# PD_MK2_Signals.net
KiCad netlist of a schematic drawn in Altium Designer
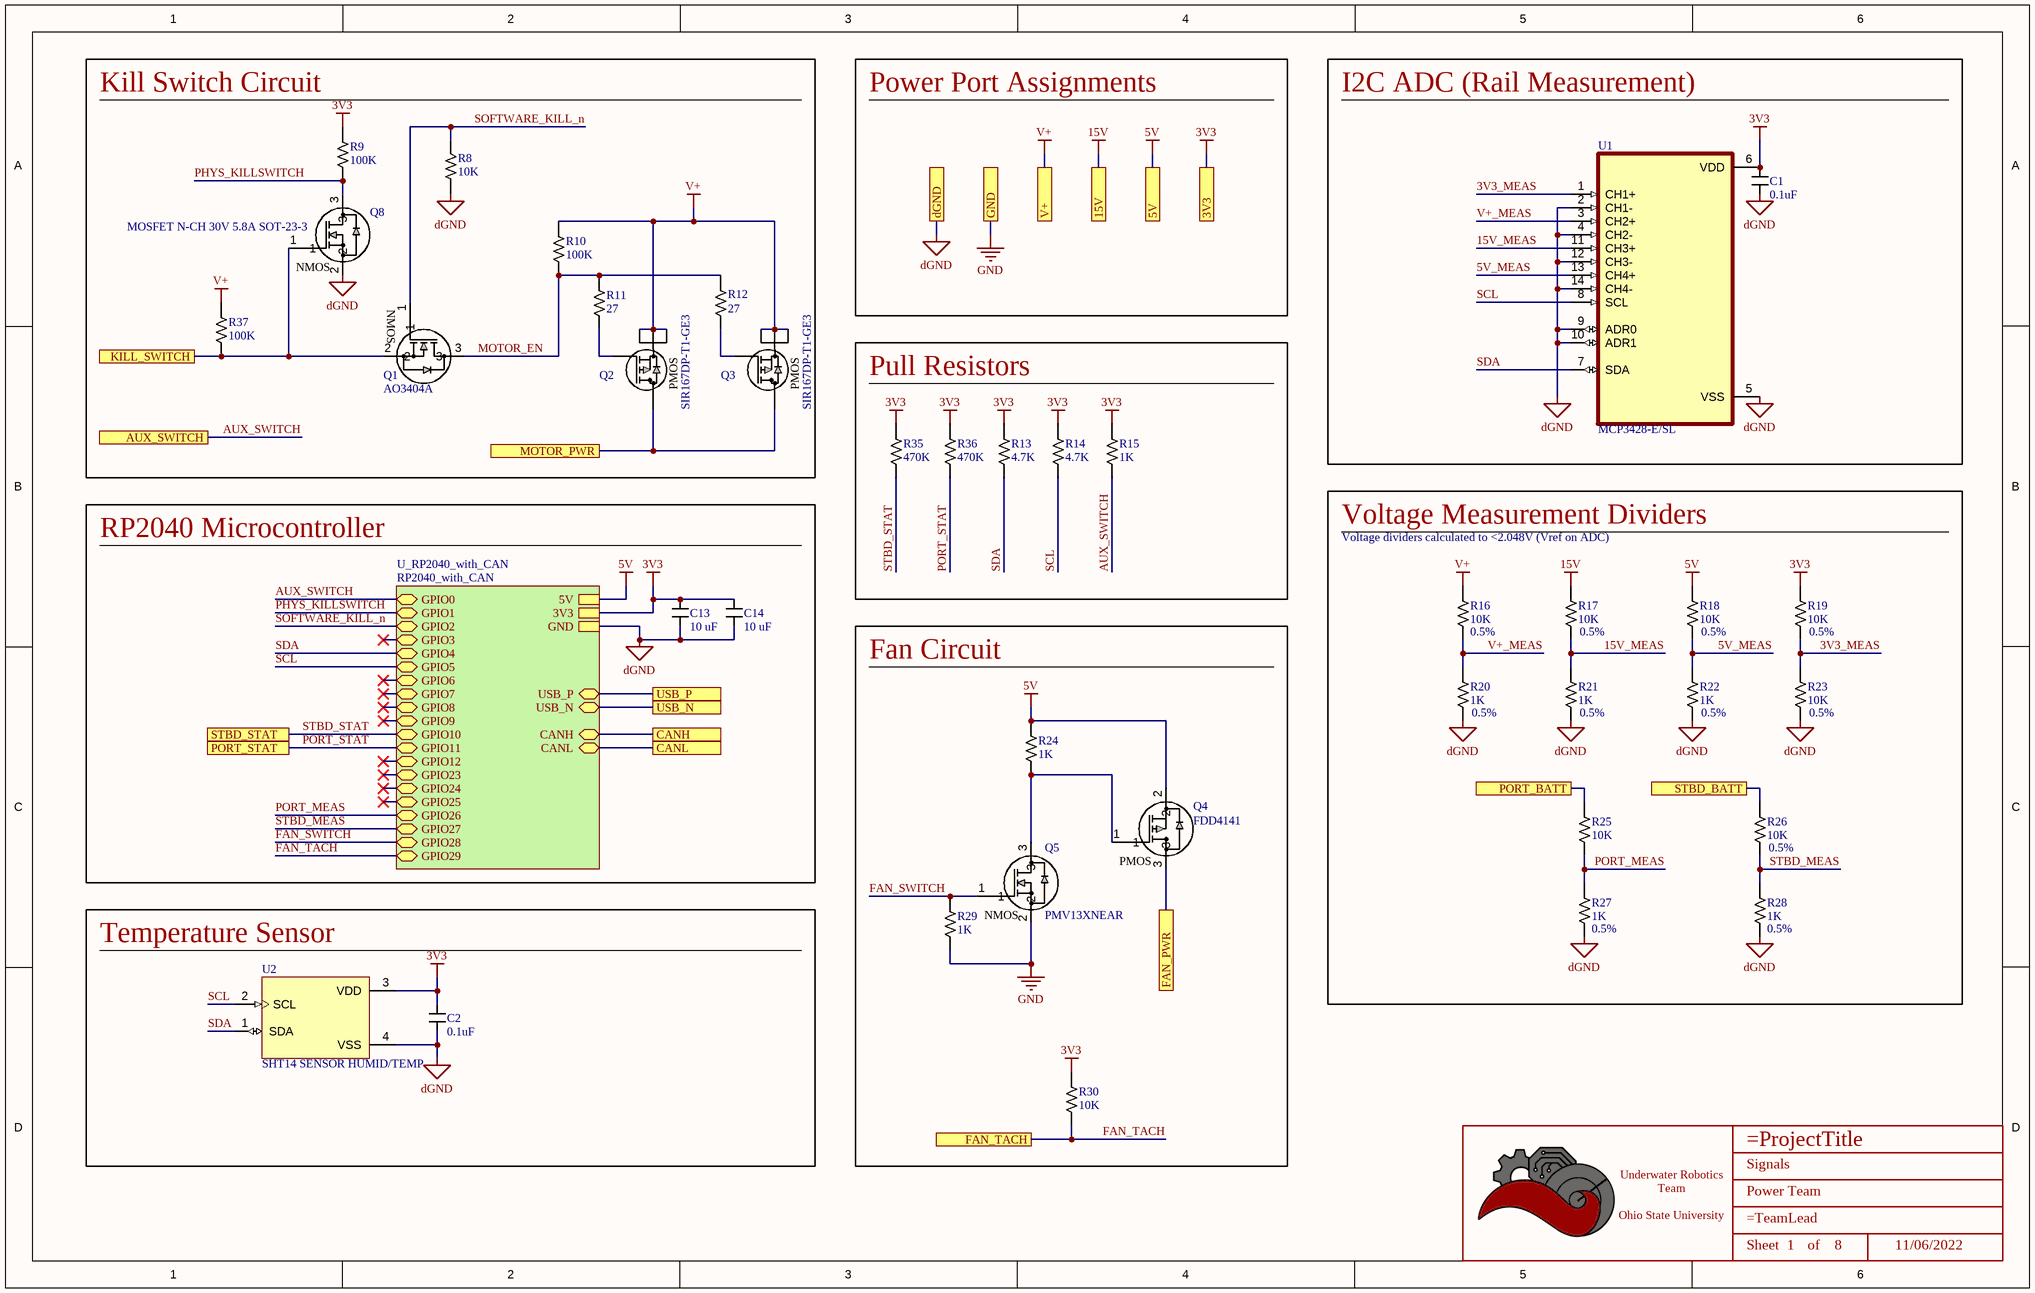
[diagram p0: PD_MK2_Signals.SchDoc]

(export (version "E")
  (design (tool "Eeschema 10.0.6"))
  (components
    (comp (ref "*")
      (value "Title_Block")
      (footprint "LOGO")
      (description "UWRT Schematic Title Block Template\r\n\r\nCreated June 2021, Dylan Trainor")
      (libsource (lib "UWRT") (part "Title_Block"))
    )
    (comp (ref "C1")
      (value "0.1uF")
      (footprint "CAPACITOR_0603")
      (description "Cap 100nF 6.3V +/-10%\r\nCeramic 0603")
      (fields
        (field (name "TOLERANCE") "+/- 10%")
        (field (name "VOLTAGE") "6.3V")
        (field (name "MADE BY") "Flip B")
      )
      (libsource (lib "Capacitors") (part "CAPACITOR_0.1uF_0603"))
    )
    (comp (ref "C2")
      (value "0.1uF")
      (footprint "CAPACITOR_0603")
      (description "Cap 100nF 6.3V +/-10%\r\nCeramic 0603")
      (fields
        (field (name "TOLERANCE") "+/- 10%")
        (field (name "VOLTAGE") "6.3V")
        (field (name "MADE BY") "Flip B")
      )
      (libsource (lib "Capacitors") (part "CAPACITOR_0.1uF_0603"))
    )
    (comp (ref "C13")
      (value "10uF Ceramic 6.3V")
      (footprint "CAPACITOR_0603")
      (description "Cap 10uF 6.3V +/-20%\r\nCeramic 0603")
      (fields
        (field (name "TOLERANCE") "+/- 20%")
        (field (name "VOLTAGE") "6.3V")
        (field (name "VALUE (UF)") "10 uF")
        (field (name "MADE BY") "Flip B")
      )
      (libsource (lib "Capacitors") (part "CAPACITOR_10uF_0603"))
    )
    (comp (ref "C14")
      (value "10uF Ceramic 6.3V")
      (footprint "CAPACITOR_0603")
      (description "Cap 10uF 6.3V +/-20%\r\nCeramic 0603")
      (fields
        (field (name "TOLERANCE") "+/- 20%")
        (field (name "VOLTAGE") "6.3V")
        (field (name "VALUE (UF)") "10 uF")
        (field (name "MADE BY") "Flip B")
      )
      (libsource (lib "Capacitors") (part "CAPACITOR_10uF_0603"))
    )
    (comp (ref "Q1")
      (value "AO3404A")
      (footprint "SOT-23-3")
      (description "N-Channel 30 V 5.8A (Ta) 1.4W (Ta) Surface Mount SOT-23-3")
      (fields (field (name "CREATED BY") "Dylan T"))
      (libsource (lib "Transistors") (part "AO3404A"))
    )
    (comp (ref "Q2")
      (value "SIR167DP-T1-GE3")
      (footprint "MOSFET_7DP-T1-GE3_VIS")
      (description "P-Channel 30 V 60A (Tc) 65.8W (Tc) Surface Mount PowerPAK® SO-8")
      (fields (field (name "COPYRIGHT") "Copyright (C) 2022 Ultra Librarian. All rights reserved."))
      (libsource (lib "Transistors") (part "SIR167DP-T1-GE3"))
    )
    (comp (ref "Q3")
      (value "SIR167DP-T1-GE3")
      (footprint "MOSFET_7DP-T1-GE3_VIS")
      (description "P-Channel 30 V 60A (Tc) 65.8W (Tc) Surface Mount PowerPAK® SO-8")
      (fields (field (name "COPYRIGHT") "Copyright (C) 2022 Ultra Librarian. All rights reserved."))
      (libsource (lib "Transistors") (part "SIR167DP-T1-GE3"))
    )
    (comp (ref "Q4")
      (value "FDD4141")
      (footprint "DPAK_ONS")
      (description "P-Channel 10.8A (Ta), 50A (Tc) 2.4W (Ta), 69W (Tc) Surface Mount D-PAK (TO-252AA)")
      (fields (field (name "CREATED BY") "Dylan T"))
      (libsource (lib "Transistors") (part "FDD4141"))
    )
    (comp (ref "Q5")
      (value "PMV13XNEAR")
      (footprint "SOT-23-3")
      (description "N-Channel 20 V 7.3A (Ta) 610mW (Ta), 8.3W (Tc) Surface Mount TO-236AB")
      (fields (field (name "CREATED BY") "Dylan T"))
      (libsource (lib "Transistors") (part "PMV13XNEAR"))
    )
    (comp (ref "Q8")
      (value "MOSFET N-CH 30V 5.8A SOT-23-3")
      (footprint "SOT-23-3")
      (description "N-Channel 30 V 5.8A (Ta) 1.4W (Ta) Surface Mount SOT-23-3")
      (fields (field (name "MANUFACTURER _PART_NUMBER") "AO3404A") (field (name "CREATED BY") "Dylan T"))
      (libsource (lib "Transistors") (part "AO3404A"))
    )
    (comp (ref "R8")
      (value "10k Ohm 5% 1/10W")
      (footprint "RESISTOR_0603")
      (description "RES 10k OHM 5% 1/10W 0603")
      (fields
        (field (name "TOLERANCE") "+/- 5%")
        (field (name "VALUE  (OHMS)") "10K")
        (field (name "MADE BY") "Robert Pafford")
      )
      (libsource (lib "Resistors") (part "RESISTOR_10K_0603"))
    )
    (comp (ref "R9")
      (value "100k Ohm 0.5% 1/10W")
      (footprint "RESISTOR_0603")
      (description "RES 100k OHM 0.5% 1/10W 0603")
      (fields
        (field (name "TOLERANCE") "+/- 0.5%")
        (field (name "VALUE  (OHMS)") "100K")
        (field (name "MADE BY") "John Ulm")
      )
      (libsource (lib "Resistors") (part "RESISTOR_100K_0.5%_0603"))
    )
    (comp (ref "R10")
      (value "100k Ohm 0.5% 1/10W")
      (footprint "RESISTOR_0603")
      (description "RES 100k OHM 0.5% 1/10W 0603")
      (fields
        (field (name "TOLERANCE") "+/- 0.5%")
        (field (name "VALUE  (OHMS)") "100K")
        (field (name "MADE BY") "John Ulm")
      )
      (libsource (lib "Resistors") (part "RESISTOR_100K_0.5%_0603"))
    )
    (comp (ref "R11")
      (value "27 Ohm 5% 1/8W")
      (footprint "RESISTOR_0603")
      (description "RES 27 OHM 5% 1/8W 0603")
      (fields
        (field (name "TOLERANCE") "+/- 5%")
        (field (name "VALUE  (OHMS)") "27")
        (field (name "MADE BY") "Robert Pafford")
      )
      (libsource (lib "Resistors") (part "RESISTOR_27_0603"))
    )
    (comp (ref "R12")
      (value "27 Ohm 5% 1/8W")
      (footprint "RESISTOR_0603")
      (description "RES 27 OHM 5% 1/8W 0603")
      (fields
        (field (name "TOLERANCE") "+/- 5%")
        (field (name "VALUE  (OHMS)") "27")
        (field (name "MADE BY") "Robert Pafford")
      )
      (libsource (lib "Resistors") (part "RESISTOR_27_0603"))
    )
    (comp (ref "R13")
      (value "4.7k Ohm 5% 1/10W")
      (footprint "RESISTOR_0603")
      (description "RES 4.7k OHM 5% 1/10W 0603")
      (fields
        (field (name "TOLERANCE") "+/- 5%")
        (field (name "VALUE  (OHMS)") "4.7K")
        (field (name "MADE BY") "Robert Pafford")
      )
      (libsource (lib "Resistors") (part "RESISTOR_4.7K_0603"))
    )
    (comp (ref "R14")
      (value "4.7k Ohm 5% 1/10W")
      (footprint "RESISTOR_0603")
      (description "RES 4.7k OHM 5% 1/10W 0603")
      (fields
        (field (name "TOLERANCE") "+/- 5%")
        (field (name "VALUE  (OHMS)") "4.7K")
        (field (name "MADE BY") "Robert Pafford")
      )
      (libsource (lib "Resistors") (part "RESISTOR_4.7K_0603"))
    )
    (comp (ref "R15")
      (value "1k Ohm 5% 1/8W")
      (footprint "RESISTOR_0603")
      (description "RES 1k OHM 5% 1/8W 0603")
      (fields
        (field (name "TOLERANCE") "+/- 5%")
        (field (name "VALUE  (OHMS)") "1K")
        (field (name "MADE BY") "Robert Pafford")
      )
      (libsource (lib "Resistors") (part "RESISTOR_1K_0603"))
    )
    (comp (ref "R16")
      (value "10k Ohm 0.5% 1/10W")
      (footprint "RESISTOR_0603")
      (description "RES 10k OHM 0.5% 1/10W 0603")
      (fields
        (field (name "TOLERANCE") "+/- 0.5%")
        (field (name "VALUE  (OHMS)") "10K")
        (field (name "MADE BY") "Robert Pafford")
      )
      (libsource (lib "Resistors") (part "RESISTOR_10K_0.5%_0603"))
    )
    (comp (ref "R17")
      (value "10k Ohm 0.5% 1/10W")
      (footprint "RESISTOR_0603")
      (description "RES 10k OHM 0.5% 1/10W 0603")
      (fields
        (field (name "TOLERANCE") "+/- 0.5%")
        (field (name "VALUE  (OHMS)") "10K")
        (field (name "MADE BY") "Robert Pafford")
      )
      (libsource (lib "Resistors") (part "RESISTOR_10K_0.5%_0603"))
    )
    (comp (ref "R18")
      (value "10k Ohm 0.5% 1/10W")
      (footprint "RESISTOR_0603")
      (description "RES 10k OHM 0.5% 1/10W 0603")
      (fields
        (field (name "TOLERANCE") "+/- 0.5%")
        (field (name "VALUE  (OHMS)") "10K")
        (field (name "MADE BY") "Robert Pafford")
      )
      (libsource (lib "Resistors") (part "RESISTOR_10K_0.5%_0603"))
    )
    (comp (ref "R19")
      (value "10k Ohm 0.5% 1/10W")
      (footprint "RESISTOR_0603")
      (description "RES 10k OHM 0.5% 1/10W 0603")
      (fields
        (field (name "TOLERANCE") "+/- 0.5%")
        (field (name "VALUE  (OHMS)") "10K")
        (field (name "MADE BY") "Robert Pafford")
      )
      (libsource (lib "Resistors") (part "RESISTOR_10K_0.5%_0603"))
    )
    (comp (ref "R20")
      (value "1k Ohm 5% 1/10W")
      (footprint "RESISTOR_0603")
      (description "RES 1k OHM 0.5% 1/10W 0603")
      (fields
        (field (name "TOLERANCE") "+/- 0.5%")
        (field (name "VALUE  (OHMS)") "1K")
        (field (name "MADE BY") "Robert Pafford")
      )
      (libsource (lib "Resistors") (part "RESISTOR_1K_0.5%_0603"))
    )
    (comp (ref "R21")
      (value "1k Ohm 5% 1/10W")
      (footprint "RESISTOR_0603")
      (description "RES 1k OHM 0.5% 1/10W 0603")
      (fields
        (field (name "TOLERANCE") "+/- 0.5%")
        (field (name "VALUE  (OHMS)") "1K")
        (field (name "MADE BY") "Robert Pafford")
      )
      (libsource (lib "Resistors") (part "RESISTOR_1K_0.5%_0603"))
    )
    (comp (ref "R22")
      (value "1k Ohm 5% 1/10W")
      (footprint "RESISTOR_0603")
      (description "RES 1k OHM 0.5% 1/10W 0603")
      (fields
        (field (name "TOLERANCE") "+/- 0.5%")
        (field (name "VALUE  (OHMS)") "1K")
        (field (name "MADE BY") "Robert Pafford")
      )
      (libsource (lib "Resistors") (part "RESISTOR_1K_0.5%_0603"))
    )
    (comp (ref "R23")
      (value "10k Ohm 0.5% 1/10W")
      (footprint "RESISTOR_0603")
      (description "RES 10k OHM 0.5% 1/10W 0603")
      (fields
        (field (name "TOLERANCE") "+/- 0.5%")
        (field (name "VALUE  (OHMS)") "10K")
        (field (name "MADE BY") "Robert Pafford")
      )
      (libsource (lib "Resistors") (part "RESISTOR_10K_0.5%_0603"))
    )
    (comp (ref "R24")
      (value "1k Ohm 5% 1/8W")
      (footprint "RESISTOR_0603")
      (description "RES 1k OHM 5% 1/8W 0603")
      (fields
        (field (name "TOLERANCE") "+/- 5%")
        (field (name "VALUE  (OHMS)") "1K")
        (field (name "MADE BY") "Robert Pafford")
      )
      (libsource (lib "Resistors") (part "RESISTOR_1K_0603"))
    )
    (comp (ref "R25")
      (value "10k Ohm 0.5% 1/10W")
      (footprint "RESISTOR_0603")
      (description "RES 10k OHM 0.5% 1/10W 0603")
      (fields
        (field (name "TOLERANCE") "+/- 0.5%")
        (field (name "VALUE  (OHMS)") "10K")
        (field (name "MADE BY") "Robert Pafford")
      )
      (libsource (lib "Resistors") (part "RESISTOR_10K_0.5%_0603"))
    )
    (comp (ref "R26")
      (value "10k Ohm 0.5% 1/10W")
      (footprint "RESISTOR_0603")
      (description "RES 10k OHM 0.5% 1/10W 0603")
      (fields
        (field (name "TOLERANCE") "+/- 0.5%")
        (field (name "VALUE  (OHMS)") "10K")
        (field (name "MADE BY") "Robert Pafford")
      )
      (libsource (lib "Resistors") (part "RESISTOR_10K_0.5%_0603"))
    )
    (comp (ref "R27")
      (value "1k Ohm 5% 1/10W")
      (footprint "RESISTOR_0603")
      (description "RES 1k OHM 0.5% 1/10W 0603")
      (fields
        (field (name "TOLERANCE") "+/- 0.5%")
        (field (name "VALUE  (OHMS)") "1K")
        (field (name "MADE BY") "Robert Pafford")
      )
      (libsource (lib "Resistors") (part "RESISTOR_1K_0.5%_0603"))
    )
    (comp (ref "R28")
      (value "1k Ohm 5% 1/10W")
      (footprint "RESISTOR_0603")
      (description "RES 1k OHM 0.5% 1/10W 0603")
      (fields
        (field (name "TOLERANCE") "+/- 0.5%")
        (field (name "VALUE  (OHMS)") "1K")
        (field (name "MADE BY") "Robert Pafford")
      )
      (libsource (lib "Resistors") (part "RESISTOR_1K_0.5%_0603"))
    )
    (comp (ref "R29")
      (value "1k Ohm 5% 1/8W")
      (footprint "RESISTOR_0603")
      (description "RES 1k OHM 5% 1/8W 0603")
      (fields
        (field (name "TOLERANCE") "+/- 5%")
        (field (name "VALUE  (OHMS)") "1K")
        (field (name "MADE BY") "Robert Pafford")
      )
      (libsource (lib "Resistors") (part "RESISTOR_1K_0603"))
    )
    (comp (ref "R30")
      (value "10k Ohm 5% 1/10W")
      (footprint "RESISTOR_0603")
      (description "RES 10k OHM 5% 1/10W 0603")
      (fields
        (field (name "TOLERANCE") "+/- 5%")
        (field (name "VALUE  (OHMS)") "10K")
        (field (name "MADE BY") "Robert Pafford")
      )
      (libsource (lib "Resistors") (part "RESISTOR_10K_0603"))
    )
    (comp (ref "R35")
      (value "470k Ohm 5% 1/10W")
      (footprint "RESISTOR_0603")
      (description "RES 470k OHM 5% 1/10W 0603")
      (fields
        (field (name "TOLERANCE") "+/- 5%")
        (field (name "VALUE  (OHMS)") "470K")
        (field (name "MADE BY") "Robert P")
      )
      (libsource (lib "Resistors") (part "RESISTOR_470K_0603"))
    )
    (comp (ref "R36")
      (value "470k Ohm 5% 1/10W")
      (footprint "RESISTOR_0603")
      (description "RES 470k OHM 5% 1/10W 0603")
      (fields
        (field (name "TOLERANCE") "+/- 5%")
        (field (name "VALUE  (OHMS)") "470K")
        (field (name "MADE BY") "Robert P")
      )
      (libsource (lib "Resistors") (part "RESISTOR_470K_0603"))
    )
    (comp (ref "R37")
      (value "100k Ohm 0.5% 1/10W")
      (footprint "RESISTOR_0603")
      (description "RES 100k OHM 0.5% 1/10W 0603")
      (fields
        (field (name "TOLERANCE") "+/- 0.5%")
        (field (name "VALUE  (OHMS)") "100K")
        (field (name "MADE BY") "John Ulm")
      )
      (libsource (lib "Resistors") (part "RESISTOR_100K_0.5%_0603"))
    )
    (comp (ref "U1")
      (value "MCP3428-E/SL")
      (footprint "SOIC127P600X175-14N")
      (description "16 Bit Analog to Digital Converter 4 Input 1 Sigma-Delta 14-SOIC")
      (fields (field (name "MF") "Microchip"))
      (libsource (lib "MCP3428-E_SL") (part "MCP3428-E/SL"))
    )
    (comp (ref "U2")
      (value "SHT14 SENSOR HUMID/TEMP")
      (footprint "XDCR_SHT41-AD1B-R2")
      (description "Digital Relative Humidity Temperature Sensor, Â±1.8 / max 2.5 %RH, Â±0.2 Â°C, Ultra-Low-Power")
      (fields (field (name "MP") "SHT41-AD1B-R2") (field (name "MF") "Sensirion"))
      (libsource (lib "Integrated Circuits") (part "SHT41-AD1B-R2"))
    )
  )
  (nets
    (net (code "1") (name "/3V3_MEAS") (class "Default")
      (node (ref "R19") (pin "2") (pinfunction "2_2") (pintype "passive"))
      (node (ref "R23") (pin "1") (pinfunction "1_1") (pintype "passive"))
      (node (ref "U1") (pin "1") (pinfunction "CH1+_1") (pintype "input"))
    )
    (net (code "2") (name "/5V_MEAS") (class "Default")
      (node (ref "R18") (pin "2") (pinfunction "2_2") (pintype "passive"))
      (node (ref "R22") (pin "1") (pinfunction "1_1") (pintype "passive"))
      (node (ref "U1") (pin "13") (pinfunction "CH4+_13") (pintype "input"))
    )
    (net (code "3") (name "/15V_MEAS") (class "Default")
      (node (ref "R17") (pin "2") (pinfunction "2_2") (pintype "passive"))
      (node (ref "R21") (pin "1") (pinfunction "1_1") (pintype "passive"))
      (node (ref "U1") (pin "11") (pinfunction "CH3+_11") (pintype "input"))
    )
    (net (code "4") (name "/AUX_SWITCH") (class "Default")
      (node (ref "R15") (pin "2") (pinfunction "2_2") (pintype "passive"))
    )
    (net (code "7") (name "/FAN_PWR") (class "Default")
      (node (ref "Q4") (pin "3") (pinfunction "3_3") (pintype "passive"))
    )
    (net (code "8") (name "/FAN_SWITCH") (class "Default")
      (node (ref "Q5") (pin "1") (pinfunction "1_1") (pintype "passive"))
      (node (ref "R29") (pin "1") (pinfunction "1_1") (pintype "passive"))
    )
    (net (code "9") (name "/FAN_TACH") (class "Default")
      (node (ref "R30") (pin "2") (pinfunction "2_2") (pintype "passive"))
    )
    (net (code "19") (name "/KILL_SWITCH") (class "Default")
      (node (ref "Q1") (pin "2") (pinfunction "2_2") (pintype "passive"))
      (node (ref "Q8") (pin "1") (pinfunction "1_1") (pintype "passive"))
      (node (ref "R37") (pin "2") (pinfunction "2_2") (pintype "passive"))
    )
    (net (code "20") (name "/MOTOR_EN") (class "Default")
      (node (ref "Q1") (pin "3") (pinfunction "3_3") (pintype "passive"))
      (node (ref "R10") (pin "2") (pinfunction "2_2") (pintype "passive"))
      (node (ref "R11") (pin "1") (pinfunction "1_1") (pintype "passive"))
      (node (ref "R12") (pin "1") (pinfunction "1_1") (pintype "passive"))
    )
    (net (code "21") (name "/MOTOR_PWR") (class "Default")
      (node (ref "Q2") (pin "D") (pinfunction "D_D") (pintype "passive"))
      (node (ref "Q3") (pin "D") (pinfunction "D_D") (pintype "passive"))
    )
    (net (code "22") (name "/PHYS_KILLSWITCH") (class "Default")
      (node (ref "Q8") (pin "3") (pinfunction "3_3") (pintype "passive"))
      (node (ref "R9") (pin "2") (pinfunction "2_2") (pintype "passive"))
    )
    (net (code "23") (name "/PORT_BATT") (class "Default")
      (node (ref "R25") (pin "1") (pinfunction "1_1") (pintype "passive"))
    )
    (net (code "24") (name "/PORT_MEAS") (class "Default")
      (node (ref "R25") (pin "2") (pinfunction "2_2") (pintype "passive"))
      (node (ref "R27") (pin "1") (pinfunction "1_1") (pintype "passive"))
    )
    (net (code "25") (name "/PORT_STAT") (class "Default")
      (node (ref "R36") (pin "2") (pinfunction "2_2") (pintype "passive"))
    )
    (net (code "26") (name "/SCL") (class "Default")
      (node (ref "R14") (pin "2") (pinfunction "2_2") (pintype "passive"))
      (node (ref "U1") (pin "8") (pinfunction "SCL_8") (pintype "input"))
      (node (ref "U2") (pin "2") (pinfunction "SCL_2") (pintype "input"))
    )
    (net (code "27") (name "/SDA") (class "Default")
      (node (ref "R13") (pin "2") (pinfunction "2_2") (pintype "passive"))
      (node (ref "U1") (pin "7") (pinfunction "SDA_7") (pintype "bidirectional"))
      (node (ref "U2") (pin "1") (pinfunction "SDA_1") (pintype "bidirectional"))
    )
    (net (code "28") (name "/SOFTWARE_KILL_n") (class "Default")
      (node (ref "Q1") (pin "1") (pinfunction "1_1") (pintype "passive"))
      (node (ref "R8") (pin "2") (pinfunction "2_2") (pintype "passive"))
    )
    (net (code "29") (name "/STBD_BATT") (class "Default")
      (node (ref "R26") (pin "1") (pinfunction "1_1") (pintype "passive"))
    )
    (net (code "30") (name "/STBD_MEAS") (class "Default")
      (node (ref "R26") (pin "2") (pinfunction "2_2") (pintype "passive"))
      (node (ref "R28") (pin "1") (pinfunction "1_1") (pintype "passive"))
    )
    (net (code "31") (name "/STBD_STAT") (class "Default")
      (node (ref "R35") (pin "2") (pinfunction "2_2") (pintype "passive"))
    )
    (net (code "34") (name "/V+_MEAS") (class "Default")
      (node (ref "R16") (pin "2") (pinfunction "2_2") (pintype "passive"))
      (node (ref "R20") (pin "1") (pinfunction "1_1") (pintype "passive"))
      (node (ref "U1") (pin "3") (pinfunction "CH2+_3") (pintype "input"))
    )
    (net (code "35") (name "3V3") (class "Default")
      (node (ref "C1") (pin "1") (pinfunction "1_1") (pintype "passive"))
      (node (ref "C13") (pin "1") (pinfunction "1_1") (pintype "passive"))
      (node (ref "C14") (pin "1") (pinfunction "1_1") (pintype "passive"))
      (node (ref "C2") (pin "1") (pinfunction "1_1") (pintype "passive"))
      (node (ref "R13") (pin "1") (pinfunction "1_1") (pintype "passive"))
      (node (ref "R14") (pin "1") (pinfunction "1_1") (pintype "passive"))
      (node (ref "R15") (pin "1") (pinfunction "1_1") (pintype "passive"))
      (node (ref "R19") (pin "1") (pinfunction "1_1") (pintype "passive"))
      (node (ref "R30") (pin "1") (pinfunction "1_1") (pintype "passive"))
      (node (ref "R35") (pin "1") (pinfunction "1_1") (pintype "passive"))
      (node (ref "R36") (pin "1") (pinfunction "1_1") (pintype "passive"))
      (node (ref "R9") (pin "1") (pinfunction "1_1") (pintype "passive"))
      (node (ref "U1") (pin "6") (pinfunction "VDD_6") (pintype "power_in"))
      (node (ref "U2") (pin "3") (pinfunction "VDD_3") (pintype "power_in"))
    )
    (net (code "36") (name "5V") (class "Default")
      (node (ref "Q4") (pin "2") (pinfunction "2_2") (pintype "passive"))
      (node (ref "R18") (pin "1") (pinfunction "1_1") (pintype "passive"))
      (node (ref "R24") (pin "1") (pinfunction "1_1") (pintype "passive"))
    )
    (net (code "37") (name "15V") (class "Default")
      (node (ref "R17") (pin "1") (pinfunction "1_1") (pintype "passive"))
    )
    (net (code "38") (name "GND") (class "Default")
      (node (ref "Q5") (pin "2") (pinfunction "2_2") (pintype "passive"))
      (node (ref "R29") (pin "2") (pinfunction "2_2") (pintype "passive"))
    )
    (net (code "39") (name "Net-(Q2-G)") (class "Default")
      (node (ref "Q2") (pin "4") (pinfunction "G_4") (pintype "passive"))
      (node (ref "R11") (pin "2") (pinfunction "2_2") (pintype "passive"))
    )
    (net (code "40") (name "Net-(Q3-G)") (class "Default")
      (node (ref "Q3") (pin "4") (pinfunction "G_4") (pintype "passive"))
      (node (ref "R12") (pin "2") (pinfunction "2_2") (pintype "passive"))
    )
    (net (code "41") (name "Net-(Q4-Pad1)") (class "Default")
      (node (ref "Q4") (pin "1") (pinfunction "1_1") (pintype "passive"))
      (node (ref "Q5") (pin "3") (pinfunction "3_3") (pintype "passive"))
      (node (ref "R24") (pin "2") (pinfunction "2_2") (pintype "passive"))
    )
    (net (code "42") (name "V+") (class "Default")
      (node (ref "Q2") (pin "1") (pinfunction "S_1") (pintype "passive"))
      (node (ref "Q2") (pin "2") (pinfunction "S_2") (pintype "passive"))
      (node (ref "Q2") (pin "3") (pinfunction "S_3") (pintype "passive"))
      (node (ref "Q3") (pin "1") (pinfunction "S_1") (pintype "passive"))
      (node (ref "Q3") (pin "2") (pinfunction "S_2") (pintype "passive"))
      (node (ref "Q3") (pin "3") (pinfunction "S_3") (pintype "passive"))
      (node (ref "R10") (pin "1") (pinfunction "1_1") (pintype "passive"))
      (node (ref "R16") (pin "1") (pinfunction "1_1") (pintype "passive"))
      (node (ref "R37") (pin "1") (pinfunction "1_1") (pintype "passive"))
    )
    (net (code "43") (name "dGND") (class "Default")
      (node (ref "C1") (pin "2") (pinfunction "2_2") (pintype "passive"))
      (node (ref "C13") (pin "2") (pinfunction "2_2") (pintype "passive"))
      (node (ref "C14") (pin "2") (pinfunction "2_2") (pintype "passive"))
      (node (ref "C2") (pin "2") (pinfunction "2_2") (pintype "passive"))
      (node (ref "Q8") (pin "2") (pinfunction "2_2") (pintype "passive"))
      (node (ref "R20") (pin "2") (pinfunction "2_2") (pintype "passive"))
      (node (ref "R21") (pin "2") (pinfunction "2_2") (pintype "passive"))
      (node (ref "R22") (pin "2") (pinfunction "2_2") (pintype "passive"))
      (node (ref "R23") (pin "2") (pinfunction "2_2") (pintype "passive"))
      (node (ref "R27") (pin "2") (pinfunction "2_2") (pintype "passive"))
      (node (ref "R28") (pin "2") (pinfunction "2_2") (pintype "passive"))
      (node (ref "R8") (pin "1") (pinfunction "1_1") (pintype "passive"))
      (node (ref "U1") (pin "10") (pinfunction "ADR1_10") (pintype "bidirectional"))
      (node (ref "U1") (pin "12") (pinfunction "CH3-_12") (pintype "input"))
      (node (ref "U1") (pin "14") (pinfunction "CH4-_14") (pintype "input"))
      (node (ref "U1") (pin "2") (pinfunction "CH1-_2") (pintype "input"))
      (node (ref "U1") (pin "4") (pinfunction "CH2-_4") (pintype "input"))
      (node (ref "U1") (pin "5") (pinfunction "VSS_5") (pintype "power_in"))
      (node (ref "U1") (pin "9") (pinfunction "ADR0_9") (pintype "bidirectional"))
      (node (ref "U2") (pin "4") (pinfunction "VSS_4") (pintype "power_in"))
    )
  )
)
